# LEDMATRIX.net
KiCad netlist of a schematic drawn in Altium Designer
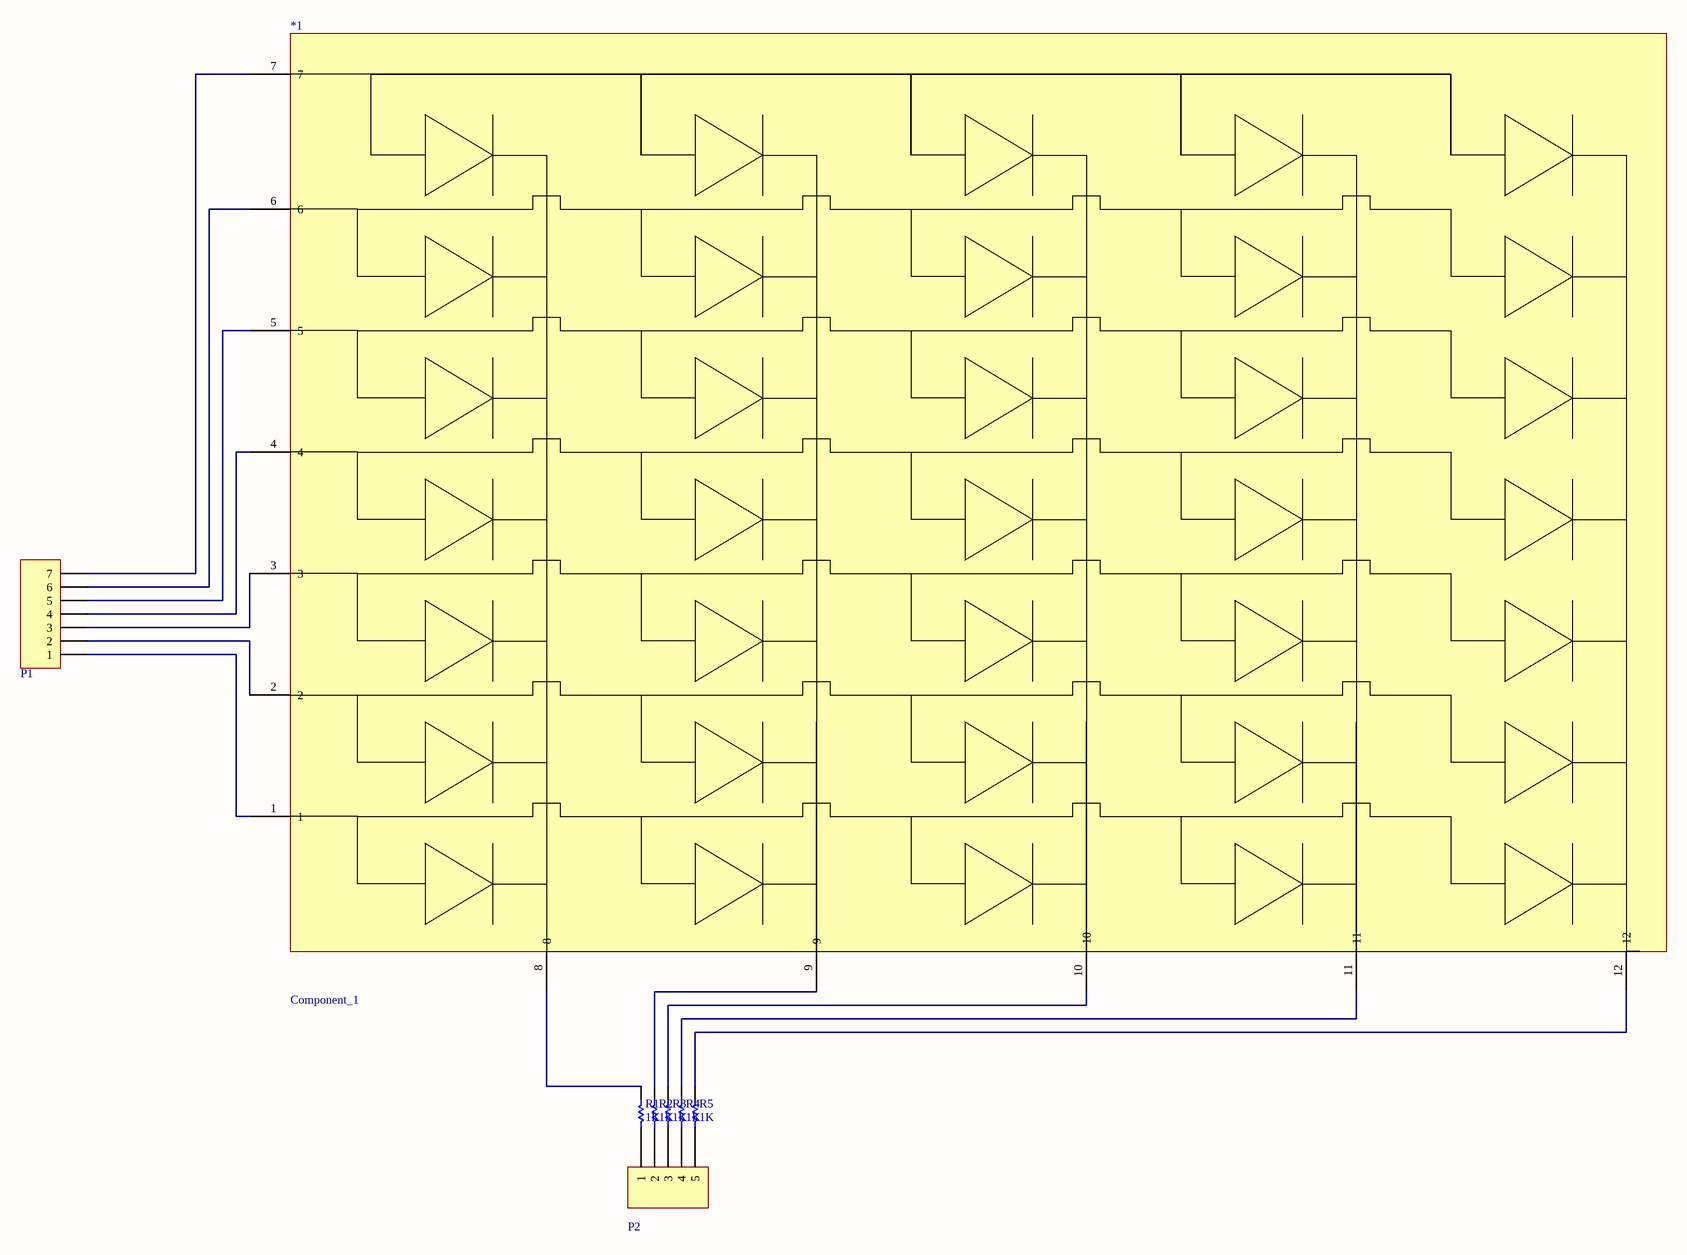
[diagram p0: LEDMATRIX.SchDoc]

(export (version "E")
  (design (tool "Eeschema 10.0.6"))
  (components
    (comp (ref "*1")
      (value "Component_1")
      (footprint "PCBComponent_1")
      (libsource (lib "LEDMATRIX") (part "Component_1"))
    )
    (comp (ref "P1")
      (value "Header 7")
      (footprint "header 7")
      (description "Header, 7-Pin")
      (fields (field (name "PUBLISHER") "Altium Limited"))
      (libsource (lib "PIF_Library") (part "Header 7"))
    )
    (comp (ref "P2")
      (value "Header 5")
      (footprint "JP5")
      (description "Header, 5-Pin")
      (fields (field (name "PUBLISHER") "Altium Limited"))
      (libsource (lib "PIF_Library") (part "Header 5"))
    )
    (comp (ref "R1")
      (value "1K")
      (footprint "RES 1/2W")
      (description "Resistor")
      (fields (field (name "Comment") "RESISTOR"))
      (libsource (lib "PIF_Library") (part "RESISTOR"))
    )
    (comp (ref "R2")
      (value "1K")
      (footprint "RES 1/2W")
      (description "Resistor")
      (fields (field (name "Comment") "RESISTOR"))
      (libsource (lib "PIF_Library") (part "RESISTOR"))
    )
    (comp (ref "R3")
      (value "1K")
      (footprint "RES 1/2W")
      (description "Resistor")
      (fields (field (name "Comment") "RESISTOR"))
      (libsource (lib "PIF_Library") (part "RESISTOR"))
    )
    (comp (ref "R4")
      (value "1K")
      (footprint "RES 1/2W")
      (description "Resistor")
      (fields (field (name "Comment") "RESISTOR"))
      (libsource (lib "PIF_Library") (part "RESISTOR"))
    )
    (comp (ref "R5")
      (value "1K")
      (footprint "RES 1/2W")
      (description "Resistor")
      (fields (field (name "Comment") "RESISTOR"))
      (libsource (lib "PIF_Library") (part "RESISTOR"))
    )
  )
  (nets
    (net (code "1") (name "Net-(*1-Pad1)") (class "Default")
      (node (ref "*1") (pin "1") (pinfunction "1_1") (pintype "power_in"))
      (node (ref "P1") (pin "1") (pinfunction "1_1") (pintype "passive"))
    )
    (net (code "2") (name "Net-(*1-Pad2)") (class "Default")
      (node (ref "*1") (pin "2") (pinfunction "2_2") (pintype "power_in"))
      (node (ref "P1") (pin "2") (pinfunction "2_2") (pintype "passive"))
    )
    (net (code "3") (name "Net-(*1-Pad3)") (class "Default")
      (node (ref "*1") (pin "3") (pinfunction "3_3") (pintype "power_in"))
      (node (ref "P1") (pin "3") (pinfunction "3_3") (pintype "passive"))
    )
    (net (code "4") (name "Net-(*1-Pad4)") (class "Default")
      (node (ref "*1") (pin "4") (pinfunction "4_4") (pintype "power_in"))
      (node (ref "P1") (pin "4") (pinfunction "4_4") (pintype "passive"))
    )
    (net (code "5") (name "Net-(*1-Pad5)") (class "Default")
      (node (ref "*1") (pin "5") (pinfunction "5_5") (pintype "power_in"))
      (node (ref "P1") (pin "5") (pinfunction "5_5") (pintype "passive"))
    )
    (net (code "6") (name "Net-(*1-Pad6)") (class "Default")
      (node (ref "*1") (pin "6") (pinfunction "6_6") (pintype "power_in"))
      (node (ref "P1") (pin "6") (pinfunction "6_6") (pintype "passive"))
    )
    (net (code "7") (name "Net-(*1-Pad7)") (class "Default")
      (node (ref "*1") (pin "7") (pinfunction "7_7") (pintype "power_in"))
      (node (ref "P1") (pin "7") (pinfunction "7_7") (pintype "passive"))
    )
    (net (code "8") (name "Net-(*1-Pad8)") (class "Default")
      (node (ref "*1") (pin "8") (pinfunction "8_8") (pintype "power_in"))
      (node (ref "R1") (pin "1") (pinfunction "1_1") (pintype "passive"))
    )
    (net (code "9") (name "Net-(*1-Pad9)") (class "Default")
      (node (ref "*1") (pin "9") (pinfunction "9_9") (pintype "power_in"))
      (node (ref "R2") (pin "1") (pinfunction "1_1") (pintype "passive"))
    )
    (net (code "10") (name "Net-(*1-Pad10)") (class "Default")
      (node (ref "*1") (pin "10") (pinfunction "10_10") (pintype "power_in"))
      (node (ref "R3") (pin "1") (pinfunction "1_1") (pintype "passive"))
    )
    (net (code "11") (name "Net-(*1-Pad11)") (class "Default")
      (node (ref "*1") (pin "11") (pinfunction "11_11") (pintype "power_in"))
      (node (ref "R4") (pin "1") (pinfunction "1_1") (pintype "passive"))
    )
    (net (code "12") (name "Net-(*1-Pad12)") (class "Default")
      (node (ref "*1") (pin "12") (pinfunction "12_12") (pintype "power_in"))
      (node (ref "R5") (pin "1") (pinfunction "1_1") (pintype "passive"))
    )
    (net (code "13") (name "Net-(P2-Pad1)") (class "Default")
      (node (ref "P2") (pin "1") (pinfunction "1_1") (pintype "passive"))
      (node (ref "R1") (pin "2") (pinfunction "2_2") (pintype "passive"))
    )
    (net (code "14") (name "Net-(P2-Pad2)") (class "Default")
      (node (ref "P2") (pin "2") (pinfunction "2_2") (pintype "passive"))
      (node (ref "R2") (pin "2") (pinfunction "2_2") (pintype "passive"))
    )
    (net (code "15") (name "Net-(P2-Pad3)") (class "Default")
      (node (ref "P2") (pin "3") (pinfunction "3_3") (pintype "passive"))
      (node (ref "R3") (pin "2") (pinfunction "2_2") (pintype "passive"))
    )
    (net (code "16") (name "Net-(P2-Pad4)") (class "Default")
      (node (ref "P2") (pin "4") (pinfunction "4_4") (pintype "passive"))
      (node (ref "R4") (pin "2") (pinfunction "2_2") (pintype "passive"))
    )
    (net (code "17") (name "Net-(P2-Pad5)") (class "Default")
      (node (ref "P2") (pin "5") (pinfunction "5_5") (pintype "passive"))
      (node (ref "R5") (pin "2") (pinfunction "2_2") (pintype "passive"))
    )
  )
)
